# Solenoid_Board.net
KiCad netlist of a schematic drawn in EAGLE
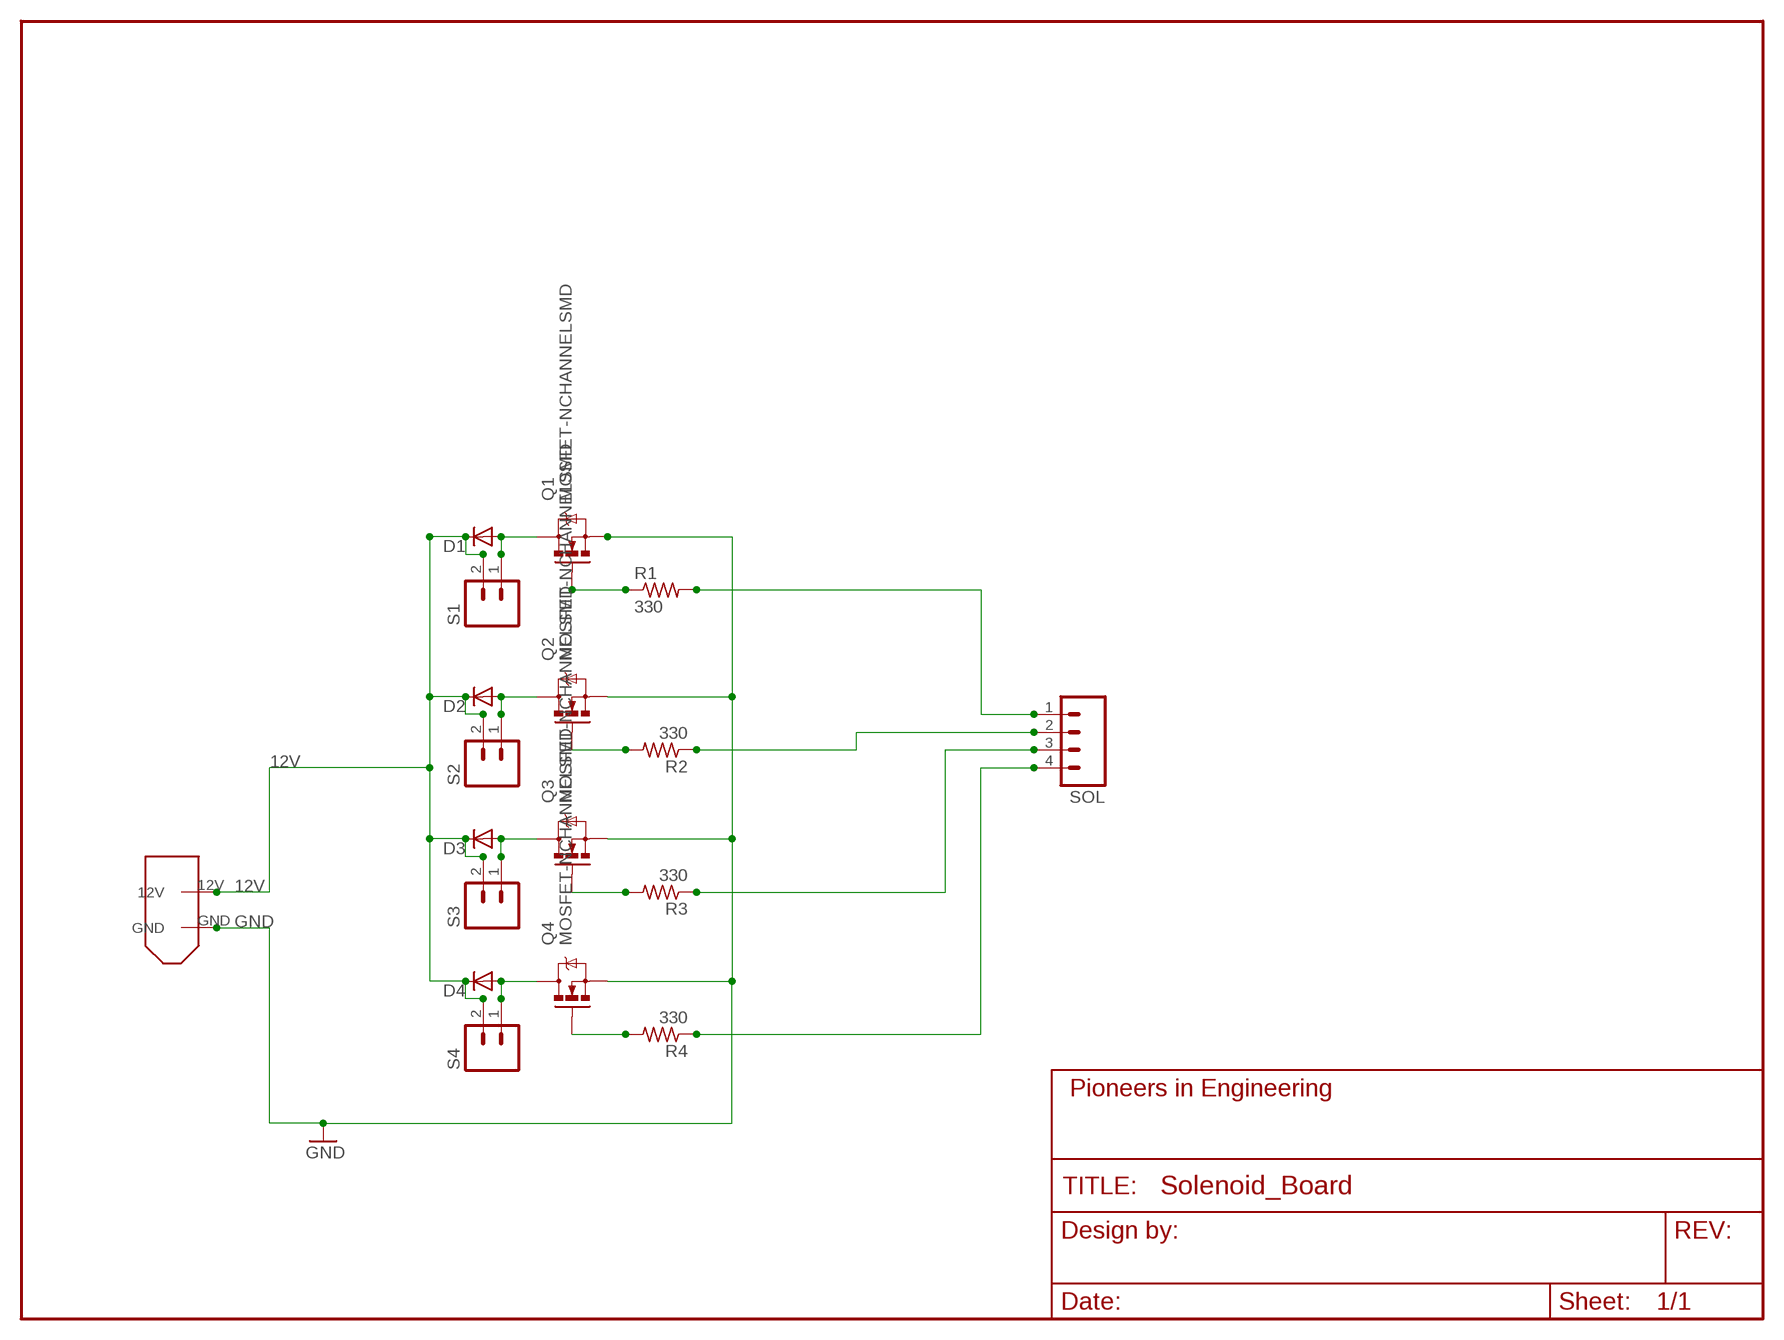
[diagram p0: schematic, sheet 1]

(export (version "E")
  (design (tool "Eeschema 10.0.6"))
  (components
    (comp (ref "D1")
      (value "DIODESMA-ALT")
      (footprint "eagle-import:SMA-DIODE_ALT")
      (libsource (lib "eagle-import") (part "DIODESMA-ALT"))
    )
    (comp (ref "D2")
      (value "DIODESMA-ALT")
      (footprint "eagle-import:SMA-DIODE_ALT")
      (libsource (lib "eagle-import") (part "DIODESMA-ALT"))
    )
    (comp (ref "D3")
      (value "DIODESMA-ALT")
      (footprint "eagle-import:SMA-DIODE_ALT")
      (libsource (lib "eagle-import") (part "DIODESMA-ALT"))
    )
    (comp (ref "D4")
      (value "DIODESMA-ALT")
      (footprint "eagle-import:SMA-DIODE_ALT")
      (libsource (lib "eagle-import") (part "DIODESMA-ALT"))
    )
    (comp (ref "Q1")
      (value "MOSFET-NCHANNELSMD")
      (footprint "eagle-import:SOT23-3")
      (libsource (lib "eagle-import") (part "MOSFET-NCHANNELSMD"))
    )
    (comp (ref "Q2")
      (value "MOSFET-NCHANNELSMD")
      (footprint "eagle-import:SOT23-3")
      (libsource (lib "eagle-import") (part "MOSFET-NCHANNELSMD"))
    )
    (comp (ref "Q3")
      (value "MOSFET-NCHANNELSMD")
      (footprint "eagle-import:SOT23-3")
      (libsource (lib "eagle-import") (part "MOSFET-NCHANNELSMD"))
    )
    (comp (ref "Q4")
      (value "MOSFET-NCHANNELSMD")
      (footprint "eagle-import:SOT23-3")
      (libsource (lib "eagle-import") (part "MOSFET-NCHANNELSMD"))
    )
    (comp (ref "R1")
      (value "330")
      (footprint "eagle-import:R0603")
      (libsource (lib "eagle-import") (part "R-US_R0603"))
    )
    (comp (ref "R2")
      (value "330")
      (footprint "eagle-import:R0603")
      (libsource (lib "eagle-import") (part "R-US_R0603"))
    )
    (comp (ref "R3")
      (value "330")
      (footprint "eagle-import:R0603")
      (libsource (lib "eagle-import") (part "R-US_R0603"))
    )
    (comp (ref "R4")
      (value "330")
      (footprint "eagle-import:R0603")
      (libsource (lib "eagle-import") (part "R-US_R0603"))
    )
    (comp (ref "S1")
      (value "M02")
      (footprint "eagle-import:1X02")
      (libsource (lib "eagle-import") (part "M02"))
    )
    (comp (ref "S2")
      (value "M02")
      (footprint "eagle-import:1X02")
      (libsource (lib "eagle-import") (part "M02"))
    )
    (comp (ref "S3")
      (value "M02")
      (footprint "eagle-import:1X02")
      (libsource (lib "eagle-import") (part "M02"))
    )
    (comp (ref "S4")
      (value "M02")
      (footprint "eagle-import:1X02")
      (libsource (lib "eagle-import") (part "M02"))
    )
    (comp (ref "SOL")
      (value "M04")
      (footprint "eagle-import:1X04")
      (libsource (lib "eagle-import") (part "M04"))
    )
    (comp (ref "U$2")
      (value "XT60CONNECTOR")
      (footprint "eagle-import:XT60CONNECTOR")
      (libsource (lib "eagle-import") (part "XT60CONNECTOR"))
    )
  )
  (nets
    (net (code "1") (name "/12V") (class "Default")
      (node (ref "D1") (pin "C") (pinfunction "C_C") (pintype "passive"))
      (node (ref "D2") (pin "C") (pinfunction "C_C") (pintype "passive"))
      (node (ref "D3") (pin "C") (pinfunction "C_C") (pintype "passive"))
      (node (ref "D4") (pin "C") (pinfunction "C_C") (pintype "passive"))
      (node (ref "S1") (pin "2") (pinfunction "2_2") (pintype "passive"))
      (node (ref "S2") (pin "2") (pinfunction "2_2") (pintype "passive"))
      (node (ref "S3") (pin "2") (pinfunction "2_2") (pintype "passive"))
      (node (ref "S4") (pin "2") (pinfunction "2_2") (pintype "passive"))
      (node (ref "U$2") (pin "12V") (pinfunction "12V_12V") (pintype "bidirectional"))
    )
    (net (code "2") (name "GND") (class "Default")
      (node (ref "Q1") (pin "2") (pinfunction "S_2") (pintype "passive"))
      (node (ref "Q2") (pin "2") (pinfunction "S_2") (pintype "passive"))
      (node (ref "Q3") (pin "2") (pinfunction "S_2") (pintype "passive"))
      (node (ref "Q4") (pin "2") (pinfunction "S_2") (pintype "passive"))
      (node (ref "U$2") (pin "GND") (pinfunction "GND_GND") (pintype "bidirectional"))
    )
    (net (code "3") (name "Net-(Q1-D)") (class "Default")
      (node (ref "D1") (pin "A") (pinfunction "A_A") (pintype "passive"))
      (node (ref "Q1") (pin "3") (pinfunction "D_3") (pintype "passive"))
      (node (ref "S1") (pin "1") (pinfunction "1_1") (pintype "passive"))
    )
    (net (code "4") (name "Net-(Q1-G)") (class "Default")
      (node (ref "Q1") (pin "1") (pinfunction "G_1") (pintype "passive"))
      (node (ref "R1") (pin "1") (pinfunction "1_1") (pintype "passive"))
    )
    (net (code "5") (name "Net-(Q2-D)") (class "Default")
      (node (ref "D2") (pin "A") (pinfunction "A_A") (pintype "passive"))
      (node (ref "Q2") (pin "3") (pinfunction "D_3") (pintype "passive"))
      (node (ref "S2") (pin "1") (pinfunction "1_1") (pintype "passive"))
    )
    (net (code "6") (name "Net-(Q2-G)") (class "Default")
      (node (ref "Q2") (pin "1") (pinfunction "G_1") (pintype "passive"))
      (node (ref "R2") (pin "2") (pinfunction "2_2") (pintype "passive"))
    )
    (net (code "7") (name "Net-(Q3-D)") (class "Default")
      (node (ref "D3") (pin "A") (pinfunction "A_A") (pintype "passive"))
      (node (ref "Q3") (pin "3") (pinfunction "D_3") (pintype "passive"))
      (node (ref "S3") (pin "1") (pinfunction "1_1") (pintype "passive"))
    )
    (net (code "8") (name "Net-(Q3-G)") (class "Default")
      (node (ref "Q3") (pin "1") (pinfunction "G_1") (pintype "passive"))
      (node (ref "R3") (pin "2") (pinfunction "2_2") (pintype "passive"))
    )
    (net (code "9") (name "Net-(Q4-D)") (class "Default")
      (node (ref "D4") (pin "A") (pinfunction "A_A") (pintype "passive"))
      (node (ref "Q4") (pin "3") (pinfunction "D_3") (pintype "passive"))
      (node (ref "S4") (pin "1") (pinfunction "1_1") (pintype "passive"))
    )
    (net (code "10") (name "Net-(Q4-G)") (class "Default")
      (node (ref "Q4") (pin "1") (pinfunction "G_1") (pintype "passive"))
      (node (ref "R4") (pin "2") (pinfunction "2_2") (pintype "passive"))
    )
    (net (code "11") (name "Net-(R1-Pad2)") (class "Default")
      (node (ref "R1") (pin "2") (pinfunction "2_2") (pintype "passive"))
      (node (ref "SOL") (pin "1") (pinfunction "1_1") (pintype "passive"))
    )
    (net (code "12") (name "Net-(R2-Pad1)") (class "Default")
      (node (ref "R2") (pin "1") (pinfunction "1_1") (pintype "passive"))
      (node (ref "SOL") (pin "2") (pinfunction "2_2") (pintype "passive"))
    )
    (net (code "13") (name "Net-(R3-Pad1)") (class "Default")
      (node (ref "R3") (pin "1") (pinfunction "1_1") (pintype "passive"))
      (node (ref "SOL") (pin "3") (pinfunction "3_3") (pintype "passive"))
    )
    (net (code "14") (name "Net-(R4-Pad1)") (class "Default")
      (node (ref "R4") (pin "1") (pinfunction "1_1") (pintype "passive"))
      (node (ref "SOL") (pin "4") (pinfunction "4_4") (pintype "passive"))
    )
  )
)
